# AD7298_12-Bit_SPI_ADC.net
KiCad netlist of a schematic drawn in Altium Designer
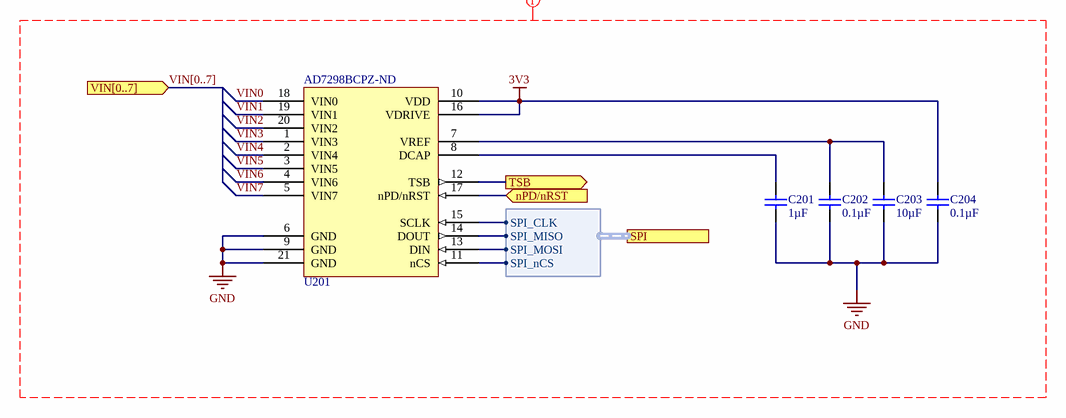
[diagram p0: AD7298 12-Bit SPI ADC.SchDoc]

(export (version "E")
  (design (tool "Eeschema 10.0.6"))
  (components
    (comp (ref "C201")
      (value "1µF")
      (footprint "TDK-CGA3E")
      (description "CAP CER 1UF 25V X7R 0603")
      (fields
        (field (name "PART NUMBER") "PC-TDK-02603")
        (field (name "MANUFACTURER PART NUMBER") "CGA3E1X7R1E105K080AC")
        (field (name "PUBLISHER") "AlbertaSat")
      )
      (libsource (lib "Database") (part "Cap"))
    )
    (comp (ref "C202")
      (value "0.1µF")
      (footprint "TDK-CGA2B")
      (description "CAP CER 0.1UF 50V X7R 0402")
      (fields
        (field (name "PART NUMBER") "PC-TDK-02259")
        (field (name "MANUFACTURER PART NUMBER") "CGA2B3X7R1H104K050BB")
        (field (name "PUBLISHER") "AlbertaSat")
      )
      (libsource (lib "Database") (part "Cap"))
    )
    (comp (ref "C203")
      (value "10µF")
      (footprint "TDK-CGA5L")
      (description "CAP CER 10UF 25V X7R 1206")
      (fields
        (field (name "PART NUMBER") "PC-TDK-02917")
        (field (name "MANUFACTURER PART NUMBER") "CGA5L1X7R1E106K160AC")
        (field (name "PUBLISHER") "AlbertaSat")
      )
      (libsource (lib "Database") (part "Cap"))
    )
    (comp (ref "C204")
      (value "0.1µF")
      (footprint "TDK-CGA2B")
      (description "CAP CER 0.1UF 50V X7R 0402")
      (fields
        (field (name "PART NUMBER") "PC-TDK-02259")
        (field (name "MANUFACTURER PART NUMBER") "CGA2B3X7R1H104K050BB")
        (field (name "PUBLISHER") "AlbertaSat")
      )
      (libsource (lib "Database") (part "Cap"))
    )
    (comp (ref "U201")
      (value "AD7298BCPZ-ND")
      (footprint "ADI-CP-20-8")
      (description "IC ADC 12BIT SAR 20LFCSP-WQ")
      (fields
        (field (name "PART NUMBER") "PU-ADI-00007")
        (field (name "MANUFACTURER PART NUMBER") "AD7298BCPZ")
        (field (name "PUBLISHER") "AlbertaSat")
      )
      (libsource (lib "Database") (part "AD7298"))
    )
  )
  (nets
    (net (code "2") (name "/SPI_CLK") (class "Default")
      (node (ref "U201") (pin "15") (pinfunction "SCLK_15") (pintype "input"))
    )
    (net (code "3") (name "/SPI_MISO") (class "Default")
      (node (ref "U201") (pin "14") (pinfunction "DOUT_14") (pintype "output"))
    )
    (net (code "4") (name "/SPI_MOSI") (class "Default")
      (node (ref "U201") (pin "13") (pinfunction "DIN_13") (pintype "input"))
    )
    (net (code "5") (name "/SPI_nCS") (class "Default")
      (node (ref "U201") (pin "11") (pinfunction "nCS_11") (pintype "input"))
    )
    (net (code "6") (name "/TSB") (class "Default")
      (node (ref "U201") (pin "12") (pinfunction "TSB_12") (pintype "output"))
    )
    (net (code "7") (name "/VIN0") (class "Default")
      (node (ref "U201") (pin "18") (pinfunction "VIN0_18") (pintype "passive"))
    )
    (net (code "8") (name "/VIN1") (class "Default")
      (node (ref "U201") (pin "19") (pinfunction "VIN1_19") (pintype "passive"))
    )
    (net (code "9") (name "/VIN2") (class "Default")
      (node (ref "U201") (pin "20") (pinfunction "VIN2_20") (pintype "passive"))
    )
    (net (code "10") (name "/VIN3") (class "Default")
      (node (ref "U201") (pin "1") (pinfunction "VIN3_1") (pintype "passive"))
    )
    (net (code "11") (name "/VIN4") (class "Default")
      (node (ref "U201") (pin "2") (pinfunction "VIN4_2") (pintype "passive"))
    )
    (net (code "12") (name "/VIN5") (class "Default")
      (node (ref "U201") (pin "3") (pinfunction "VIN5_3") (pintype "passive"))
    )
    (net (code "13") (name "/VIN6") (class "Default")
      (node (ref "U201") (pin "4") (pinfunction "VIN6_4") (pintype "passive"))
    )
    (net (code "14") (name "/VIN7") (class "Default")
      (node (ref "U201") (pin "5") (pinfunction "VIN7_5") (pintype "passive"))
    )
    (net (code "16") (name "/nPD{slash}nRST") (class "Default")
      (node (ref "U201") (pin "17") (pinfunction "nPD/nRST_17") (pintype "input"))
    )
    (net (code "18") (name "3V3") (class "Default")
      (node (ref "C204") (pin "1") (pinfunction "1_1") (pintype "passive"))
      (node (ref "U201") (pin "10") (pinfunction "VDD_10") (pintype "passive"))
      (node (ref "U201") (pin "16") (pinfunction "VDRIVE_16") (pintype "passive"))
    )
    (net (code "19") (name "GND") (class "Default")
      (node (ref "C201") (pin "1") (pinfunction "1_1") (pintype "passive"))
      (node (ref "C202") (pin "2") (pinfunction "2_2") (pintype "passive"))
      (node (ref "C203") (pin "2") (pinfunction "2_2") (pintype "passive"))
      (node (ref "C204") (pin "2") (pinfunction "2_2") (pintype "passive"))
      (node (ref "U201") (pin "21") (pinfunction "GND_21") (pintype "passive"))
      (node (ref "U201") (pin "6") (pinfunction "GND_6") (pintype "passive"))
      (node (ref "U201") (pin "9") (pinfunction "GND_9") (pintype "passive"))
    )
    (net (code "20") (name "Net-(U201-DCAP)") (class "Default")
      (node (ref "C201") (pin "2") (pinfunction "2_2") (pintype "passive"))
      (node (ref "U201") (pin "8") (pinfunction "DCAP_8") (pintype "passive"))
    )
    (net (code "21") (name "Net-(U201-VREF)") (class "Default")
      (node (ref "C202") (pin "1") (pinfunction "1_1") (pintype "passive"))
      (node (ref "C203") (pin "1") (pinfunction "1_1") (pintype "passive"))
      (node (ref "U201") (pin "7") (pinfunction "VREF_7") (pintype "passive"))
    )
  )
)
